# Sterilise.net
KiCad netlist of a schematic drawn in Altium Designer
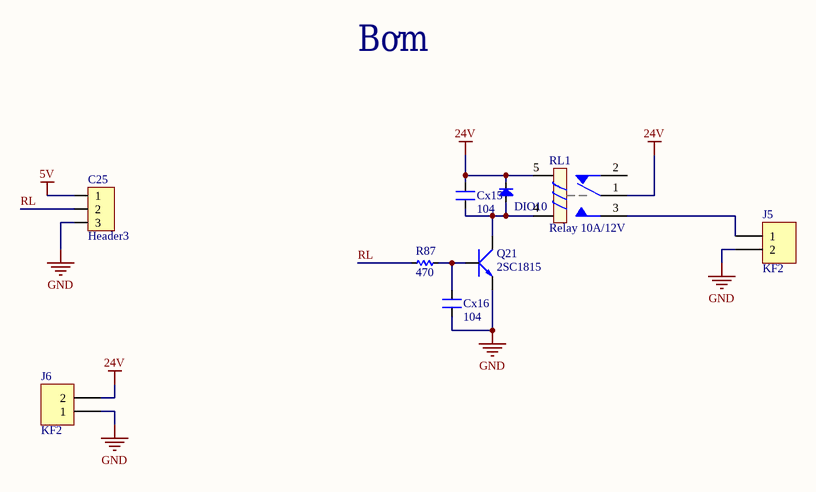
[diagram p0: Sterilise.SchDoc]

(export (version "E")
  (design (tool "Eeschema 10.0.6"))
  (components
    (comp (ref "C25")
      (value "Header3")
      (footprint "Header3")
      (description "Header IDC, 3 x 1 Pin Vertical 2.54mm Pitch (Non-Boxed, Male)")
      (fields
        (field (name "MANUFACTURER") "Würth Elektronik eiSos GmbH")
        (field (name "PARTNO") "613002143121")
        (field (name "CREATED BY") "Karrer Zheng")
      )
      (libsource (lib "LIBRARY") (part "Header3"))
    )
    (comp (ref "Cx15") (value "104") (footprint "CN-SMD-0805") (libsource (lib "LIBRARY") (part "CN")))
    (comp (ref "Cx16") (value "104") (footprint "CN-SMD-0805") (libsource (lib "LIBRARY") (part "CN")))
    (comp (ref "DIO10")
      (value "Diode SMD")
      (footprint "DIO-SMD-106")
      (description "Default Diode")
      (fields (field (name "PUBLISHER") "Altium Limited"))
      (libsource (lib "LIBRARY") (part "Diode SMD"))
    )
    (comp (ref "J5")
      (value "KF2")
      (footprint "KF2-7.62")
      (fields
        (field (name "MANUFACTURER") "Würth Elektronik eiSos GmbH")
        (field (name "PARTNO") "691103110002")
        (field (name "CREATED BY") "Karrer Zheng")
      )
      (libsource (lib "LIBRARY") (part "KF2"))
    )
    (comp (ref "J6")
      (value "KF2")
      (footprint "KF2-7.62")
      (fields
        (field (name "MANUFACTURER") "Würth Elektronik eiSos GmbH")
        (field (name "PARTNO") "691103110002")
        (field (name "CREATED BY") "Karrer Zheng")
      )
      (libsource (lib "") (part "KF2_1"))
    )
    (comp (ref "Q21")
      (value "2SC1815")
      (footprint "SOT23-321")
      (description "NPN 600mW, ECB")
      (libsource (lib "LIBRARY") (part "2SC1815"))
    )
    (comp (ref "R87")
      (value "470")
      (footprint "RES-SMD-0805")
      (description "Resistor")
      (fields
        (field (name "MANUFACTURER") "Generic Components")
        (field (name "PUBLISHER") "Altium Hobart Technology Centre")
      )
      (libsource (lib "LIBRARY") (part "Res-SMD"))
    )
    (comp (ref "RL1")
      (value "Relay 10A/12V")
      (footprint "RELAY 5")
      (description "Relay SPDT,10A - 12VDC 5 Pin")
      (libsource (lib "LIBRARY") (part "Relay 5"))
    )
  )
  (nets
    (net (code "1") (name "/RL") (class "Default")
      (node (ref "C25") (pin "2") (pinfunction "2_2") (pintype "passive"))
      (node (ref "R87") (pin "2") (pinfunction "2_2") (pintype "passive"))
    )
    (net (code "2") (name "5V") (class "Default")
      (node (ref "C25") (pin "1") (pinfunction "1_1") (pintype "passive"))
    )
    (net (code "3") (name "24V") (class "Default")
      (node (ref "Cx15") (pin "2") (pinfunction "2_2") (pintype "passive"))
      (node (ref "DIO10") (pin "2") (pinfunction "K_2") (pintype "passive"))
      (node (ref "J6") (pin "2") (pinfunction "2_2") (pintype "passive"))
      (node (ref "RL1") (pin "1") (pinfunction "1_1") (pintype "passive"))
      (node (ref "RL1") (pin "5") (pinfunction "5_5") (pintype "passive"))
    )
    (net (code "4") (name "GND") (class "Default")
      (node (ref "C25") (pin "3") (pinfunction "3_3") (pintype "passive"))
      (node (ref "Cx16") (pin "1") (pinfunction "1_1") (pintype "passive"))
      (node (ref "J5") (pin "2") (pinfunction "2_2") (pintype "passive"))
      (node (ref "J6") (pin "1") (pinfunction "1_1") (pintype "passive"))
      (node (ref "Q21") (pin "1") (pinfunction "E_1") (pintype "passive"))
    )
    (net (code "5") (name "Net-(DIO10-A)") (class "Default")
      (node (ref "Cx15") (pin "1") (pinfunction "1_1") (pintype "passive"))
      (node (ref "DIO10") (pin "1") (pinfunction "A_1") (pintype "passive"))
      (node (ref "Q21") (pin "2") (pinfunction "C_2") (pintype "passive"))
      (node (ref "RL1") (pin "4") (pinfunction "4_4") (pintype "passive"))
    )
    (net (code "6") (name "Net-(J5-Pad1)") (class "Default")
      (node (ref "J5") (pin "1") (pinfunction "1_1") (pintype "passive"))
      (node (ref "RL1") (pin "3") (pinfunction "3_3") (pintype "passive"))
    )
    (net (code "7") (name "Net-(Q21-B)") (class "Default")
      (node (ref "Cx16") (pin "2") (pinfunction "2_2") (pintype "passive"))
      (node (ref "Q21") (pin "3") (pinfunction "B_3") (pintype "passive"))
      (node (ref "R87") (pin "1") (pinfunction "1_1") (pintype "passive"))
    )
    (net (code "8") (name "unconnected-(RL1-Pad2)") (class "Default")
      (node (ref "RL1") (pin "2") (pinfunction "2_2") (pintype "passive"))
    )
  )
)
